# 00A-022_FRDM_Protoboard.net
KiCad netlist of a schematic drawn in EAGLE
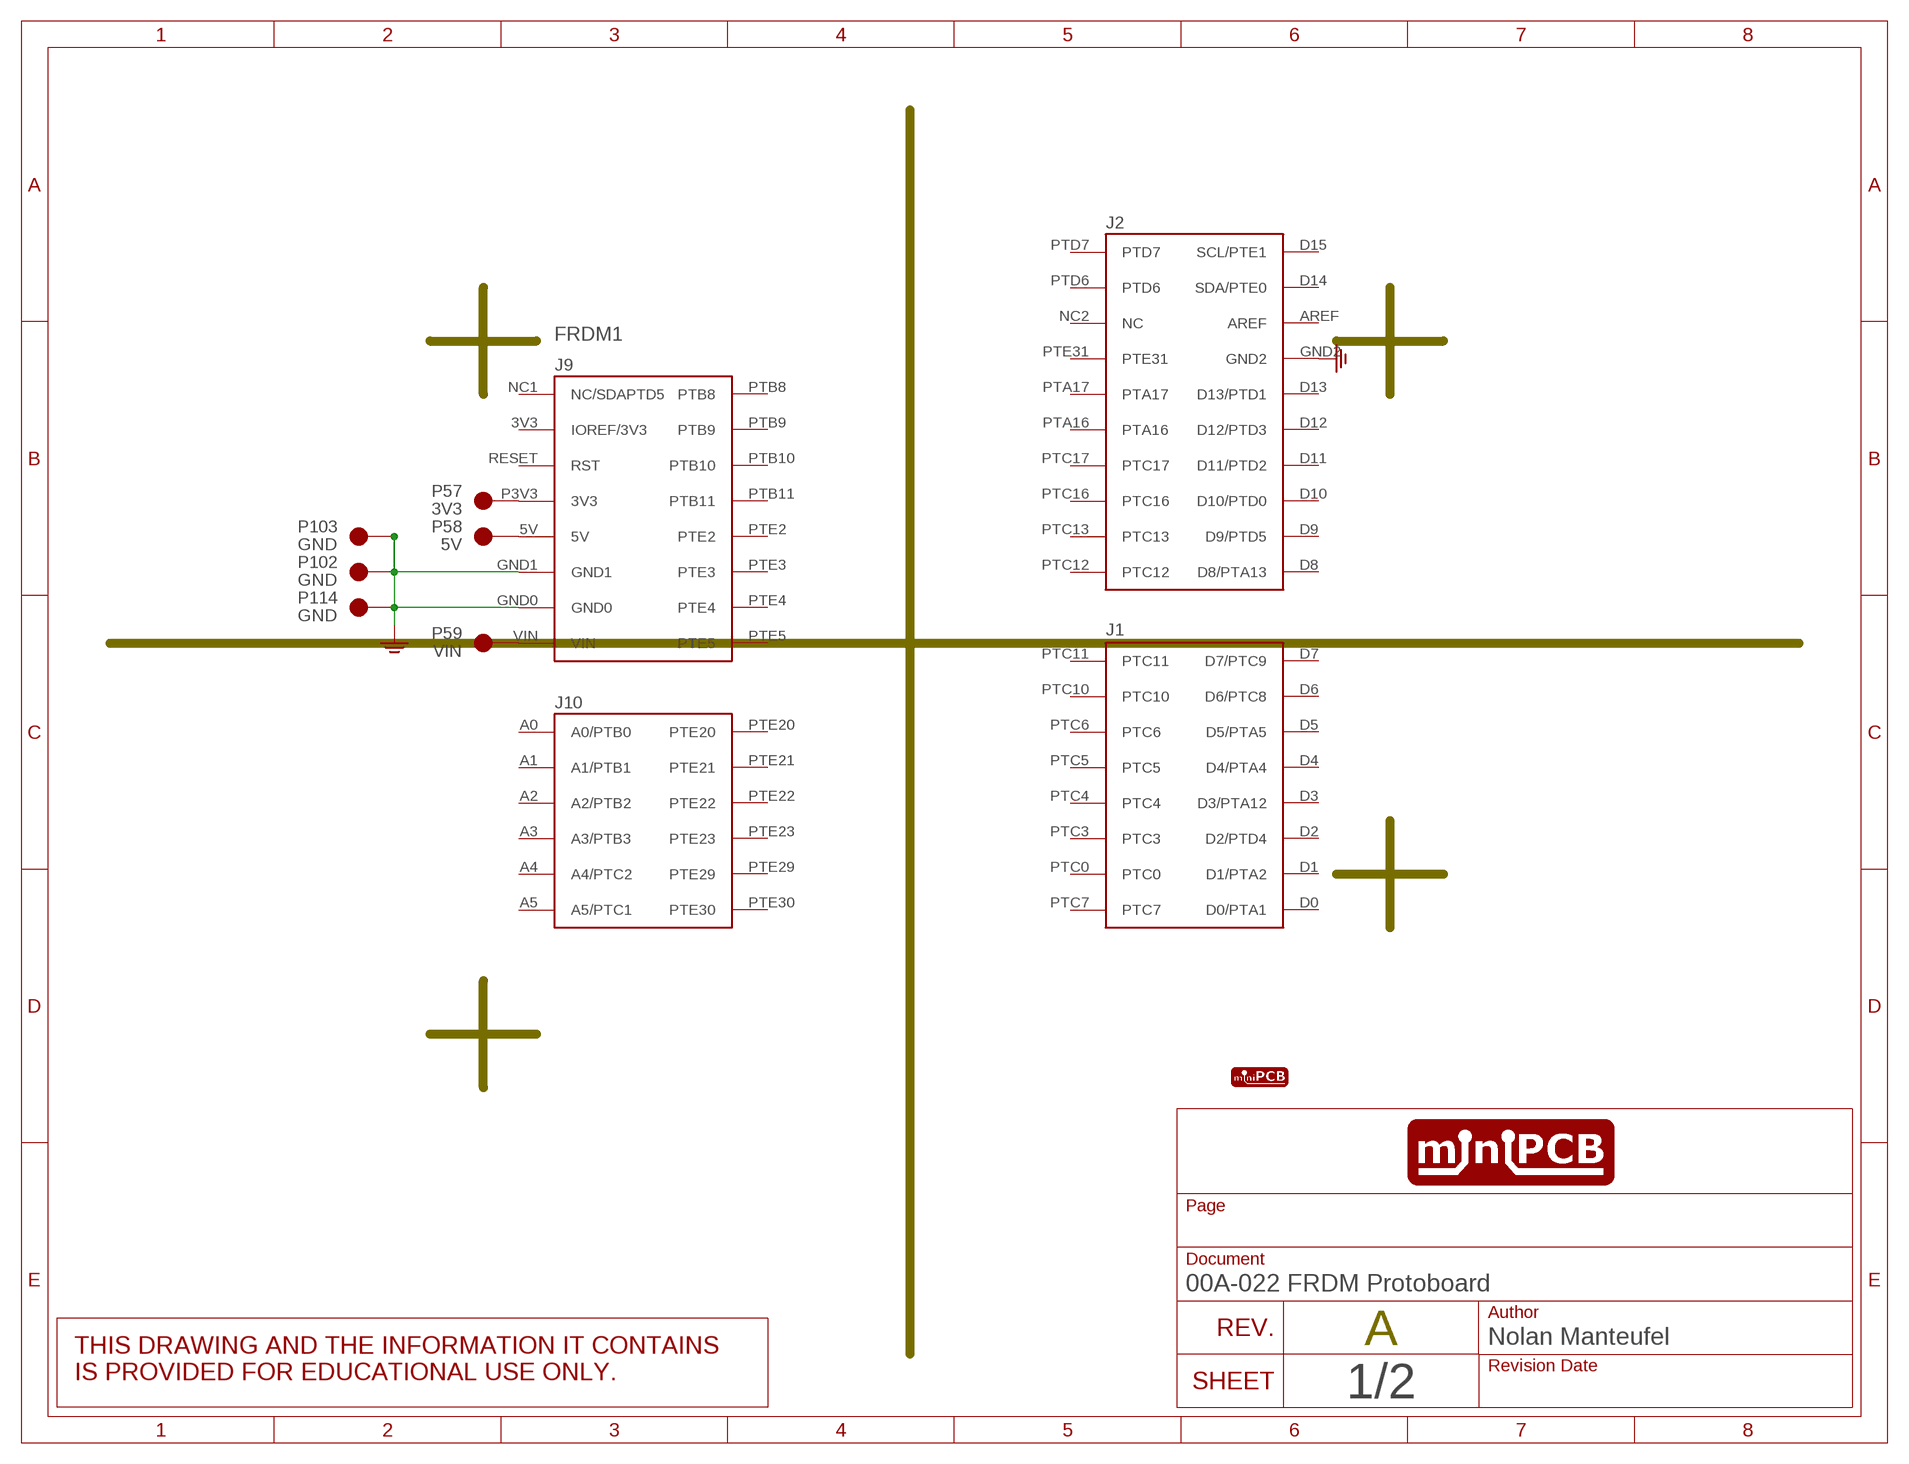
[diagram p0: schematic, sheet 1]
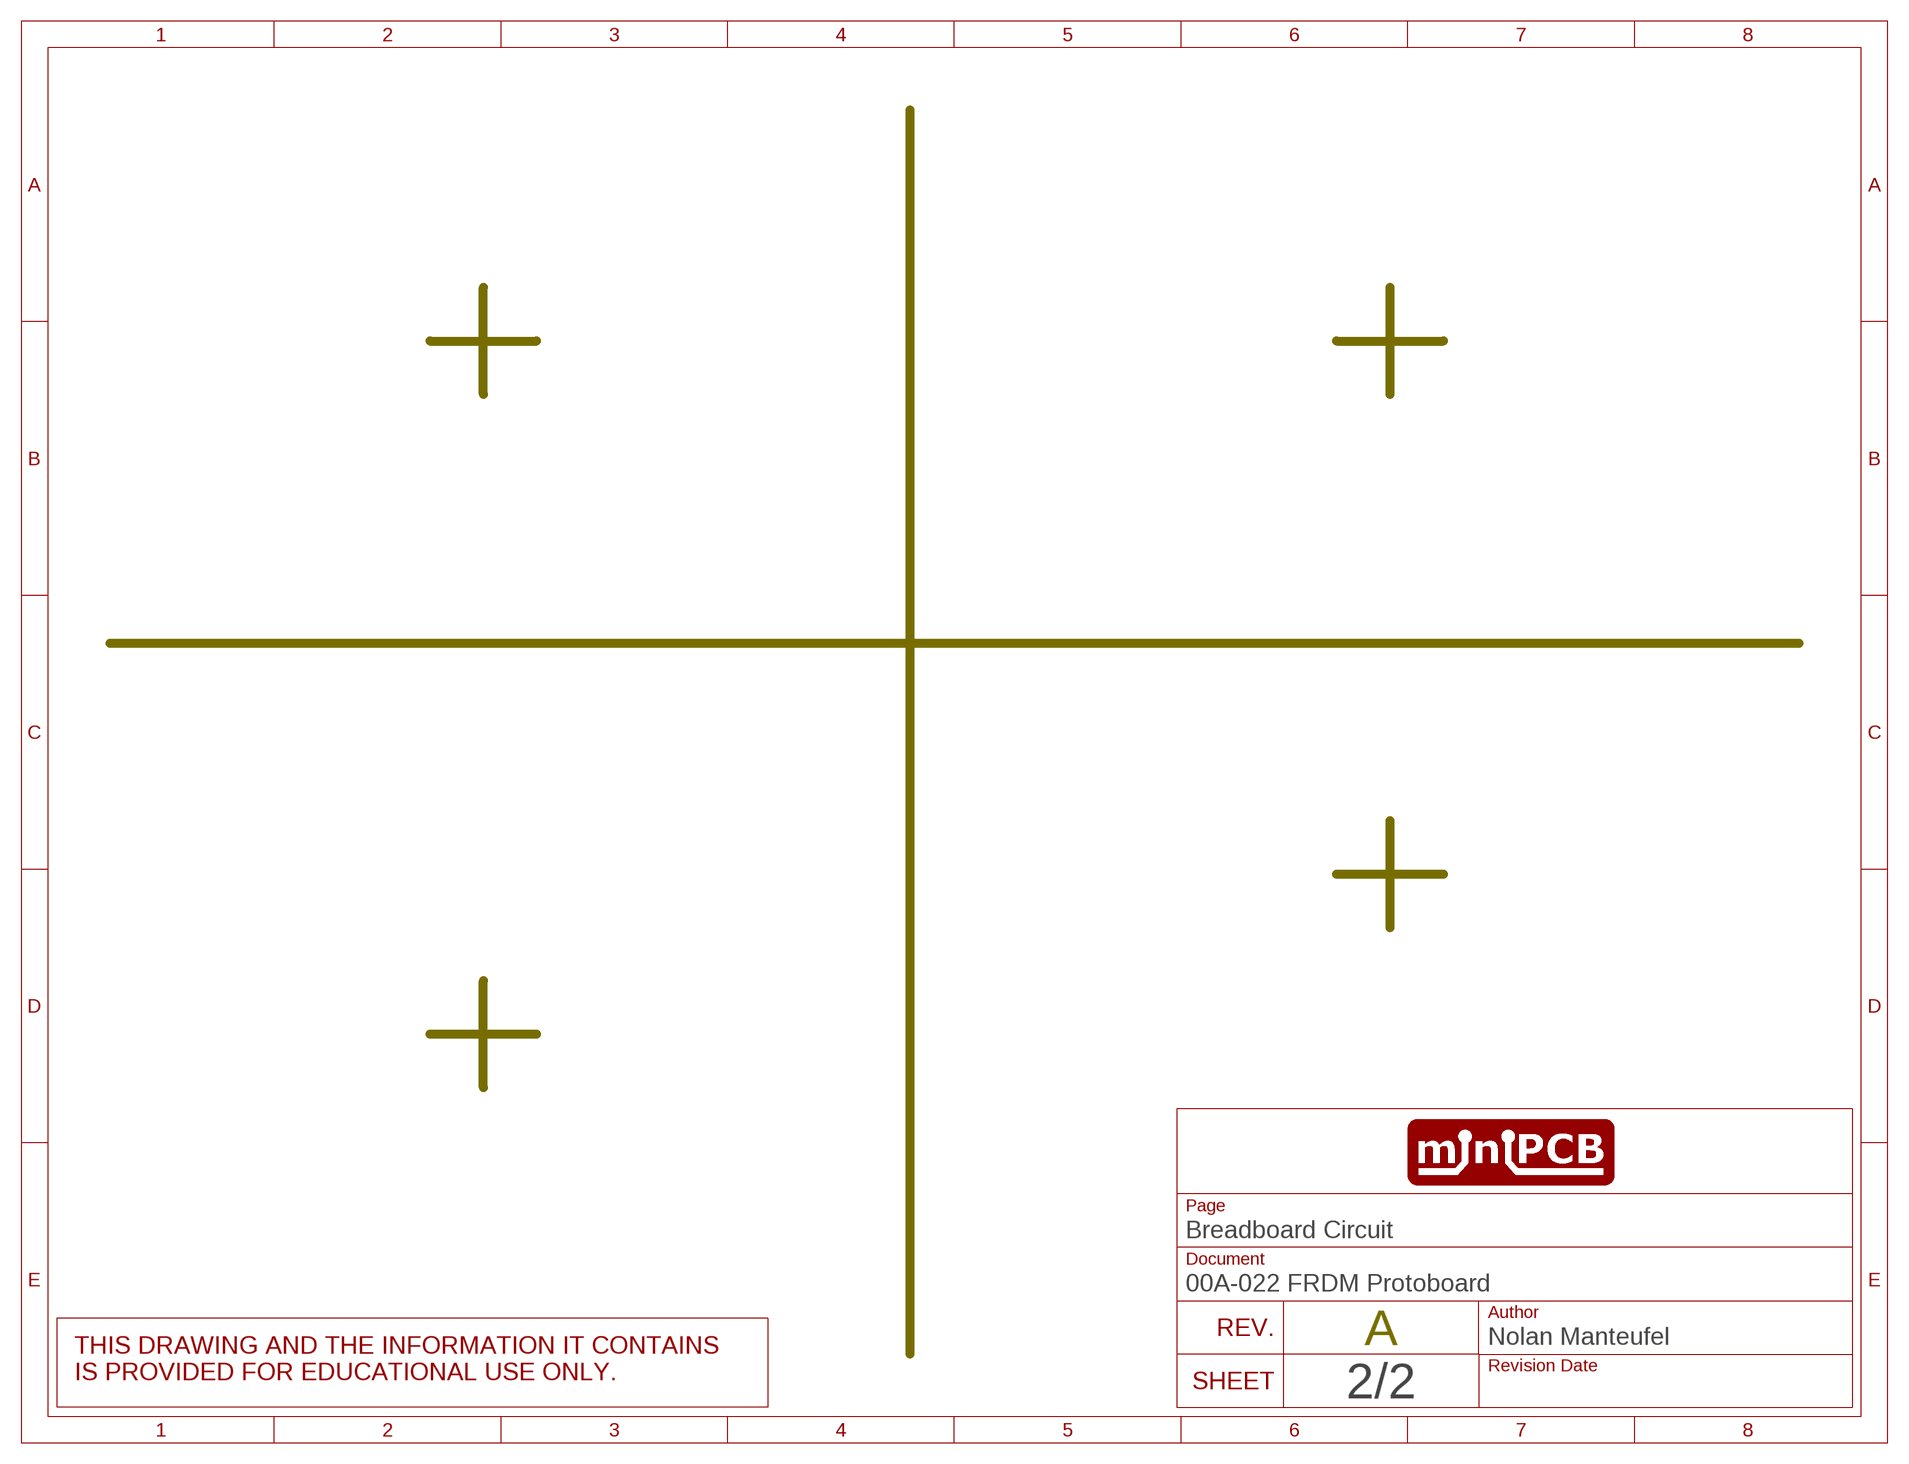
[diagram p1: schematic, sheet 2]

(export (version "E")
  (design (tool "Eeschema 10.0.6"))
  (components
    (comp (ref "FRDM1")
      (value "FRDM-KL25ZNORMAL")
      (footprint "eagle-import:FRDM_KL25Z_NORMAL")
      (fields (field (name "MF") "NXP USA") (field (name "MP") "FRDM-KL25Z"))
      (libsource (lib "eagle-import") (part "FRDM-KL25ZNORMAL"))
    )
    (comp (ref "P57")
      (value "3V3")
      (footprint "eagle-import:PINS_1-3P_VALUE")
      (libsource (lib "eagle-import") (part "PINS_13P_VALUE"))
    )
    (comp (ref "P58")
      (value "5V")
      (footprint "eagle-import:PINS_1-3P_VALUE")
      (libsource (lib "eagle-import") (part "PINS_13P_VALUE"))
    )
    (comp (ref "P59")
      (value "VIN")
      (footprint "eagle-import:PINS_1-3P_VALUE")
      (libsource (lib "eagle-import") (part "PINS_13P_VALUE"))
    )
    (comp (ref "P102")
      (value "GND")
      (footprint "eagle-import:PINS_1-3P_VALUE")
      (libsource (lib "eagle-import") (part "PINS_13P_VALUE"))
    )
    (comp (ref "P103")
      (value "GND")
      (footprint "eagle-import:PINS_1-3P_VALUE")
      (libsource (lib "eagle-import") (part "PINS_13P_VALUE"))
    )
    (comp (ref "P114")
      (value "GND")
      (footprint "eagle-import:PINS_1-3P_VALUE")
      (libsource (lib "eagle-import") (part "PINS_13P_VALUE"))
    )
    (comp (ref "U$1")
      (value "MINIPCB_LOGO")
      (footprint "eagle-import:MINIPCB-LOGO")
      (libsource (lib "eagle-import") (part "MINIPCB_LOGO"))
    )
  )
  (nets
    (net (code "1") (name "GND") (class "Default")
      (node (ref "FRDM1") (pin "GND0") (pinfunction "GND0_GND0") (pintype "bidirectional"))
      (node (ref "FRDM1") (pin "GND1") (pinfunction "GND1_GND1") (pintype "bidirectional"))
      (node (ref "FRDM1") (pin "GND2") (pinfunction "GND2_GND2") (pintype "bidirectional"))
      (node (ref "P102") (pin "1") (pinfunction "1_1") (pintype "bidirectional"))
      (node (ref "P102") (pin "2") (pinfunction "1_2") (pintype "bidirectional"))
      (node (ref "P102") (pin "3") (pinfunction "1_3") (pintype "bidirectional"))
      (node (ref "P103") (pin "1") (pinfunction "1_1") (pintype "bidirectional"))
      (node (ref "P103") (pin "2") (pinfunction "1_2") (pintype "bidirectional"))
      (node (ref "P103") (pin "3") (pinfunction "1_3") (pintype "bidirectional"))
      (node (ref "P114") (pin "1") (pinfunction "1_1") (pintype "bidirectional"))
      (node (ref "P114") (pin "2") (pinfunction "1_2") (pintype "bidirectional"))
      (node (ref "P114") (pin "3") (pinfunction "1_3") (pintype "bidirectional"))
    )
    (net (code "2") (name "Net-(FRDM1-3V3)") (class "Default")
      (node (ref "FRDM1") (pin "P3V3") (pinfunction "3V3_P3V3") (pintype "bidirectional"))
      (node (ref "P57") (pin "1") (pinfunction "1_1") (pintype "bidirectional"))
      (node (ref "P57") (pin "2") (pinfunction "1_2") (pintype "bidirectional"))
      (node (ref "P57") (pin "3") (pinfunction "1_3") (pintype "bidirectional"))
    )
    (net (code "3") (name "Net-(FRDM1-Pad5V)") (class "Default")
      (node (ref "FRDM1") (pin "5V") (pinfunction "5V_5V") (pintype "bidirectional"))
      (node (ref "P58") (pin "1") (pinfunction "1_1") (pintype "bidirectional"))
      (node (ref "P58") (pin "2") (pinfunction "1_2") (pintype "bidirectional"))
      (node (ref "P58") (pin "3") (pinfunction "1_3") (pintype "bidirectional"))
    )
    (net (code "4") (name "Net-(FRDM1-PadVIN)") (class "Default")
      (node (ref "FRDM1") (pin "VIN") (pinfunction "VIN_VIN") (pintype "bidirectional"))
      (node (ref "P59") (pin "1") (pinfunction "1_1") (pintype "bidirectional"))
      (node (ref "P59") (pin "2") (pinfunction "1_2") (pintype "bidirectional"))
      (node (ref "P59") (pin "3") (pinfunction "1_3") (pintype "bidirectional"))
    )
    (net (code "5") (name "unconnected-(FRDM1-A0{slash}PTB0-PadA0)") (class "Default")
      (node (ref "FRDM1") (pin "A0") (pinfunction "A0/PTB0_A0") (pintype "bidirectional"))
    )
    (net (code "6") (name "unconnected-(FRDM1-A1{slash}PTB1-PadA1)") (class "Default")
      (node (ref "FRDM1") (pin "A1") (pinfunction "A1/PTB1_A1") (pintype "bidirectional"))
    )
    (net (code "7") (name "unconnected-(FRDM1-A2{slash}PTB2-PadA2)") (class "Default")
      (node (ref "FRDM1") (pin "A2") (pinfunction "A2/PTB2_A2") (pintype "bidirectional"))
    )
    (net (code "8") (name "unconnected-(FRDM1-A3{slash}PTB3-PadA3)") (class "Default")
      (node (ref "FRDM1") (pin "A3") (pinfunction "A3/PTB3_A3") (pintype "bidirectional"))
    )
    (net (code "9") (name "unconnected-(FRDM1-A4{slash}PTC2-PadA4)") (class "Default")
      (node (ref "FRDM1") (pin "A4") (pinfunction "A4/PTC2_A4") (pintype "bidirectional"))
    )
    (net (code "10") (name "unconnected-(FRDM1-A5{slash}PTC1-PadA5)") (class "Default")
      (node (ref "FRDM1") (pin "A5") (pinfunction "A5/PTC1_A5") (pintype "bidirectional"))
    )
    (net (code "11") (name "unconnected-(FRDM1-D0{slash}PTA1-PadD0)") (class "Default")
      (node (ref "FRDM1") (pin "D0") (pinfunction "D0/PTA1_D0") (pintype "bidirectional"))
    )
    (net (code "12") (name "unconnected-(FRDM1-D1{slash}PTA2-PadD1)") (class "Default")
      (node (ref "FRDM1") (pin "D1") (pinfunction "D1/PTA2_D1") (pintype "bidirectional"))
    )
    (net (code "13") (name "unconnected-(FRDM1-D2{slash}PTD4-PadD2)") (class "Default")
      (node (ref "FRDM1") (pin "D2") (pinfunction "D2/PTD4_D2") (pintype "bidirectional"))
    )
    (net (code "14") (name "unconnected-(FRDM1-D3{slash}PTA12-PadD3)") (class "Default")
      (node (ref "FRDM1") (pin "D3") (pinfunction "D3/PTA12_D3") (pintype "bidirectional"))
    )
    (net (code "15") (name "unconnected-(FRDM1-D4{slash}PTA4-PadD4)") (class "Default")
      (node (ref "FRDM1") (pin "D4") (pinfunction "D4/PTA4_D4") (pintype "bidirectional"))
    )
    (net (code "16") (name "unconnected-(FRDM1-D5{slash}PTA5-PadD5)") (class "Default")
      (node (ref "FRDM1") (pin "D5") (pinfunction "D5/PTA5_D5") (pintype "bidirectional"))
    )
    (net (code "17") (name "unconnected-(FRDM1-D6{slash}PTC8-PadD6)") (class "Default")
      (node (ref "FRDM1") (pin "D6") (pinfunction "D6/PTC8_D6") (pintype "bidirectional"))
    )
    (net (code "18") (name "unconnected-(FRDM1-D7{slash}PTC9-PadD7)") (class "Default")
      (node (ref "FRDM1") (pin "D7") (pinfunction "D7/PTC9_D7") (pintype "bidirectional"))
    )
    (net (code "19") (name "unconnected-(FRDM1-D8{slash}PTA13-PadD8)") (class "Default")
      (node (ref "FRDM1") (pin "D8") (pinfunction "D8/PTA13_D8") (pintype "bidirectional"))
    )
    (net (code "20") (name "unconnected-(FRDM1-D9{slash}PTD5-PadD9)") (class "Default")
      (node (ref "FRDM1") (pin "D9") (pinfunction "D9/PTD5_D9") (pintype "bidirectional"))
    )
    (net (code "21") (name "unconnected-(FRDM1-D10{slash}PTD0-PadD10)") (class "Default")
      (node (ref "FRDM1") (pin "D10") (pinfunction "D10/PTD0_D10") (pintype "bidirectional"))
    )
    (net (code "22") (name "unconnected-(FRDM1-D11{slash}PTD2-PadD11)") (class "Default")
      (node (ref "FRDM1") (pin "D11") (pinfunction "D11/PTD2_D11") (pintype "bidirectional"))
    )
    (net (code "23") (name "unconnected-(FRDM1-D12{slash}PTD3-PadD12)") (class "Default")
      (node (ref "FRDM1") (pin "D12") (pinfunction "D12/PTD3_D12") (pintype "bidirectional"))
    )
    (net (code "24") (name "unconnected-(FRDM1-D13{slash}PTD1-PadD13)") (class "Default")
      (node (ref "FRDM1") (pin "D13") (pinfunction "D13/PTD1_D13") (pintype "bidirectional"))
    )
    (net (code "25") (name "unconnected-(FRDM1-IOREF{slash}3V3-Pad3V3)") (class "Default")
      (node (ref "FRDM1") (pin "3V3") (pinfunction "IOREF/3V3_3V3") (pintype "bidirectional"))
    )
    (net (code "26") (name "unconnected-(FRDM1-NC-PadNC2)") (class "Default")
      (node (ref "FRDM1") (pin "NC2") (pinfunction "NC_NC2") (pintype "bidirectional"))
    )
    (net (code "27") (name "unconnected-(FRDM1-NC{slash}SDAPTD5-PadNC1)") (class "Default")
      (node (ref "FRDM1") (pin "NC1") (pinfunction "NC/SDAPTD5_NC1") (pintype "bidirectional"))
    )
    (net (code "28") (name "unconnected-(FRDM1-PadAREF)") (class "Default")
      (node (ref "FRDM1") (pin "AREF") (pinfunction "AREF_AREF") (pintype "bidirectional"))
    )
    (net (code "29") (name "unconnected-(FRDM1-PadPTA16)") (class "Default")
      (node (ref "FRDM1") (pin "PTA16") (pinfunction "PTA16_PTA16") (pintype "bidirectional"))
    )
    (net (code "30") (name "unconnected-(FRDM1-PadPTA17)") (class "Default")
      (node (ref "FRDM1") (pin "PTA17") (pinfunction "PTA17_PTA17") (pintype "bidirectional"))
    )
    (net (code "31") (name "unconnected-(FRDM1-PadPTB8)") (class "Default")
      (node (ref "FRDM1") (pin "PTB8") (pinfunction "PTB8_PTB8") (pintype "bidirectional"))
    )
    (net (code "32") (name "unconnected-(FRDM1-PadPTB9)") (class "Default")
      (node (ref "FRDM1") (pin "PTB9") (pinfunction "PTB9_PTB9") (pintype "bidirectional"))
    )
    (net (code "33") (name "unconnected-(FRDM1-PadPTB10)") (class "Default")
      (node (ref "FRDM1") (pin "PTB10") (pinfunction "PTB10_PTB10") (pintype "bidirectional"))
    )
    (net (code "34") (name "unconnected-(FRDM1-PadPTB11)") (class "Default")
      (node (ref "FRDM1") (pin "PTB11") (pinfunction "PTB11_PTB11") (pintype "bidirectional"))
    )
    (net (code "35") (name "unconnected-(FRDM1-PadPTC0)") (class "Default")
      (node (ref "FRDM1") (pin "PTC0") (pinfunction "PTC0_PTC0") (pintype "bidirectional"))
    )
    (net (code "36") (name "unconnected-(FRDM1-PadPTC3)") (class "Default")
      (node (ref "FRDM1") (pin "PTC3") (pinfunction "PTC3_PTC3") (pintype "bidirectional"))
    )
    (net (code "37") (name "unconnected-(FRDM1-PadPTC4)") (class "Default")
      (node (ref "FRDM1") (pin "PTC4") (pinfunction "PTC4_PTC4") (pintype "bidirectional"))
    )
    (net (code "38") (name "unconnected-(FRDM1-PadPTC5)") (class "Default")
      (node (ref "FRDM1") (pin "PTC5") (pinfunction "PTC5_PTC5") (pintype "bidirectional"))
    )
    (net (code "39") (name "unconnected-(FRDM1-PadPTC6)") (class "Default")
      (node (ref "FRDM1") (pin "PTC6") (pinfunction "PTC6_PTC6") (pintype "bidirectional"))
    )
    (net (code "40") (name "unconnected-(FRDM1-PadPTC7)") (class "Default")
      (node (ref "FRDM1") (pin "PTC7") (pinfunction "PTC7_PTC7") (pintype "bidirectional"))
    )
    (net (code "41") (name "unconnected-(FRDM1-PadPTC10)") (class "Default")
      (node (ref "FRDM1") (pin "PTC10") (pinfunction "PTC10_PTC10") (pintype "bidirectional"))
    )
    (net (code "42") (name "unconnected-(FRDM1-PadPTC11)") (class "Default")
      (node (ref "FRDM1") (pin "PTC11") (pinfunction "PTC11_PTC11") (pintype "bidirectional"))
    )
    (net (code "43") (name "unconnected-(FRDM1-PadPTC12)") (class "Default")
      (node (ref "FRDM1") (pin "PTC12") (pinfunction "PTC12_PTC12") (pintype "bidirectional"))
    )
    (net (code "44") (name "unconnected-(FRDM1-PadPTC13)") (class "Default")
      (node (ref "FRDM1") (pin "PTC13") (pinfunction "PTC13_PTC13") (pintype "bidirectional"))
    )
    (net (code "45") (name "unconnected-(FRDM1-PadPTC16)") (class "Default")
      (node (ref "FRDM1") (pin "PTC16") (pinfunction "PTC16_PTC16") (pintype "bidirectional"))
    )
    (net (code "46") (name "unconnected-(FRDM1-PadPTC17)") (class "Default")
      (node (ref "FRDM1") (pin "PTC17") (pinfunction "PTC17_PTC17") (pintype "bidirectional"))
    )
    (net (code "47") (name "unconnected-(FRDM1-PadPTD6)") (class "Default")
      (node (ref "FRDM1") (pin "PTD6") (pinfunction "PTD6_PTD6") (pintype "bidirectional"))
    )
    (net (code "48") (name "unconnected-(FRDM1-PadPTD7)") (class "Default")
      (node (ref "FRDM1") (pin "PTD7") (pinfunction "PTD7_PTD7") (pintype "bidirectional"))
    )
    (net (code "49") (name "unconnected-(FRDM1-PadPTE2)") (class "Default")
      (node (ref "FRDM1") (pin "PTE2") (pinfunction "PTE2_PTE2") (pintype "bidirectional"))
    )
    (net (code "50") (name "unconnected-(FRDM1-PadPTE3)") (class "Default")
      (node (ref "FRDM1") (pin "PTE3") (pinfunction "PTE3_PTE3") (pintype "bidirectional"))
    )
    (net (code "51") (name "unconnected-(FRDM1-PadPTE4)") (class "Default")
      (node (ref "FRDM1") (pin "PTE4") (pinfunction "PTE4_PTE4") (pintype "bidirectional"))
    )
    (net (code "52") (name "unconnected-(FRDM1-PadPTE5)") (class "Default")
      (node (ref "FRDM1") (pin "PTE5") (pinfunction "PTE5_PTE5") (pintype "bidirectional"))
    )
    (net (code "53") (name "unconnected-(FRDM1-PadPTE20)") (class "Default")
      (node (ref "FRDM1") (pin "PTE20") (pinfunction "PTE20_PTE20") (pintype "bidirectional"))
    )
    (net (code "54") (name "unconnected-(FRDM1-PadPTE21)") (class "Default")
      (node (ref "FRDM1") (pin "PTE21") (pinfunction "PTE21_PTE21") (pintype "bidirectional"))
    )
    (net (code "55") (name "unconnected-(FRDM1-PadPTE22)") (class "Default")
      (node (ref "FRDM1") (pin "PTE22") (pinfunction "PTE22_PTE22") (pintype "bidirectional"))
    )
    (net (code "56") (name "unconnected-(FRDM1-PadPTE23)") (class "Default")
      (node (ref "FRDM1") (pin "PTE23") (pinfunction "PTE23_PTE23") (pintype "bidirectional"))
    )
    (net (code "57") (name "unconnected-(FRDM1-PadPTE29)") (class "Default")
      (node (ref "FRDM1") (pin "PTE29") (pinfunction "PTE29_PTE29") (pintype "bidirectional"))
    )
    (net (code "58") (name "unconnected-(FRDM1-PadPTE30)") (class "Default")
      (node (ref "FRDM1") (pin "PTE30") (pinfunction "PTE30_PTE30") (pintype "bidirectional"))
    )
    (net (code "59") (name "unconnected-(FRDM1-PadPTE31)") (class "Default")
      (node (ref "FRDM1") (pin "PTE31") (pinfunction "PTE31_PTE31") (pintype "bidirectional"))
    )
    (net (code "60") (name "unconnected-(FRDM1-RST-PadRESET)") (class "Default")
      (node (ref "FRDM1") (pin "RESET") (pinfunction "RST_RESET") (pintype "bidirectional"))
    )
    (net (code "61") (name "unconnected-(FRDM1-SCL{slash}PTE1-PadD15)") (class "Default")
      (node (ref "FRDM1") (pin "D15") (pinfunction "SCL/PTE1_D15") (pintype "bidirectional"))
    )
    (net (code "62") (name "unconnected-(FRDM1-SDA{slash}PTE0-PadD14)") (class "Default")
      (node (ref "FRDM1") (pin "D14") (pinfunction "SDA/PTE0_D14") (pintype "bidirectional"))
    )
  )
)
